# Universal_receiver.net
KiCad netlist of a schematic drawn in Altium Designer
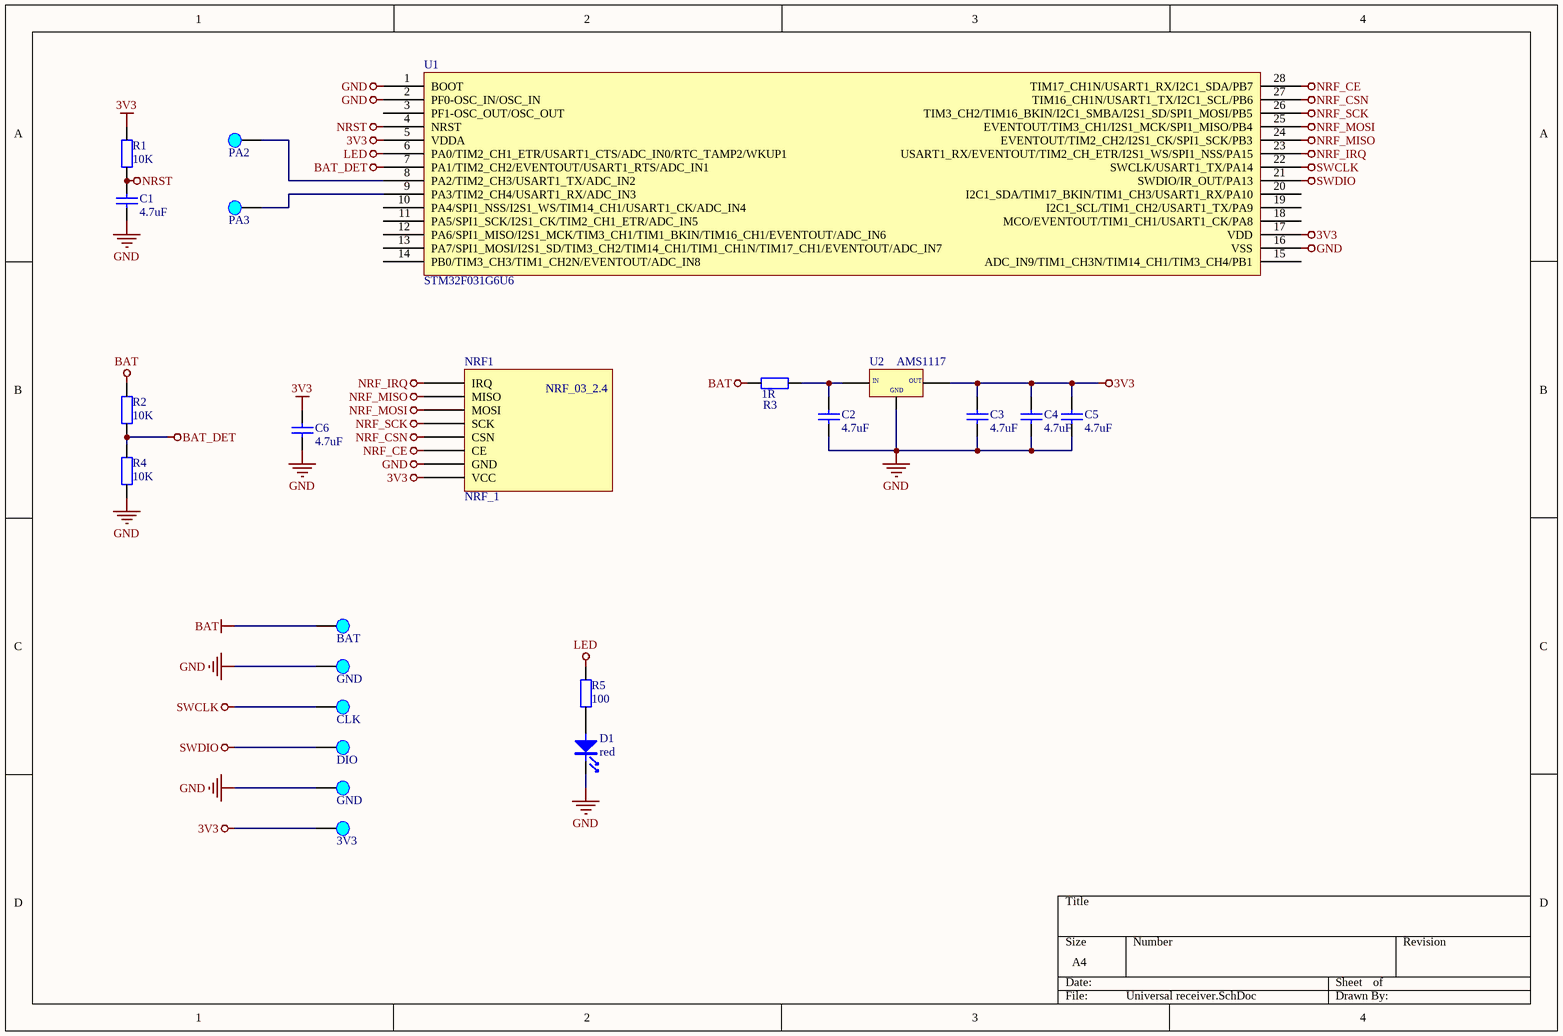
[diagram p0: Universal receiver.SchDoc]

(export (version "E")
  (design (tool "Eeschema 10.0.6"))
  (components
    (comp (ref "1")
      (value "3V3")
      (footprint "Pad_B")
      (fields (field (name "_REMARKS") "3V3"))
      (libsource (lib "元件库") (part "Pad"))
    )
    (comp (ref "BAT1")
      (value "BAT")
      (footprint "Pad_B")
      (fields (field (name "_REMARKS") "BAT"))
      (libsource (lib "元件库") (part "Pad"))
    )
    (comp (ref "C1")
      (value "4.7uF")
      (footprint "Watch Max:电容_C0603")
      (fields (field (name "C") "4.7uF"))
      (libsource (lib "WatchX") (part "cap"))
    )
    (comp (ref "C2")
      (value "4.7uF")
      (footprint "Watch Max:电容_C0603")
      (fields (field (name "C") "4.7uF"))
      (libsource (lib "WatchX") (part "cap"))
    )
    (comp (ref "C3")
      (value "4.7uF")
      (footprint "Watch Max:电容_C0603")
      (fields (field (name "C") "4.7uF"))
      (libsource (lib "WatchX") (part "cap"))
    )
    (comp (ref "C4")
      (value "4.7uF")
      (footprint "Watch Max:电容_C0603")
      (fields (field (name "C") "4.7uF"))
      (libsource (lib "WatchX") (part "cap"))
    )
    (comp (ref "C5")
      (value "4.7uF")
      (footprint "Watch Max:电容_C0603")
      (fields (field (name "C") "4.7uF"))
      (libsource (lib "WatchX") (part "cap"))
    )
    (comp (ref "C6")
      (value "4.7uF")
      (footprint "Watch Max:电容_C0603")
      (fields (field (name "C") "4.7uF"))
      (libsource (lib "WatchX") (part "cap"))
    )
    (comp (ref "CLK1")
      (value "CLK")
      (footprint "Pad_B")
      (fields (field (name "_REMARKS") "CLK"))
      (libsource (lib "元件库") (part "Pad"))
    )
    (comp (ref "D1")
      (value "red")
      (footprint "LED_0603")
      (libsource (lib "altium-import") (part "root_0_LED_"))
    )
    (comp (ref "DIO1")
      (value "DIO")
      (footprint "Pad_B")
      (fields (field (name "_REMARKS") "DIO"))
      (libsource (lib "元件库") (part "Pad"))
    )
    (comp (ref "GND1")
      (value "GND")
      (footprint "Pad_B")
      (fields (field (name "_REMARKS") "GND"))
      (libsource (lib "元件库") (part "Pad"))
    )
    (comp (ref "GND2")
      (value "GND")
      (footprint "Pad_B")
      (fields (field (name "_REMARKS") "GND"))
      (libsource (lib "元件库") (part "Pad"))
    )
    (comp (ref "NRF1") (value "NRF_1") (footprint "NRF-1") (libsource (lib "Schlib1") (part "NRF_1")))
    (comp (ref "PA1")
      (value "PA2")
      (footprint "Pad_B")
      (fields (field (name "_REMARKS") "PA2"))
      (libsource (lib "元件库") (part "Pad"))
    )
    (comp (ref "PA2")
      (value "PA3")
      (footprint "Pad_B")
      (fields (field (name "_REMARKS") "PA3"))
      (libsource (lib "元件库") (part "Pad"))
    )
    (comp (ref "R1")
      (value "10K")
      (footprint "电阻_R0603")
      (fields (field (name "R") "10K"))
      (libsource (lib "元件库") (part "Res"))
    )
    (comp (ref "R2")
      (value "10K")
      (footprint "电阻_R0603")
      (fields (field (name "R") "10K"))
      (libsource (lib "元件库") (part "Res"))
    )
    (comp (ref "R3")
      (value "1R")
      (footprint "电阻_R0603")
      (fields (field (name "R") "1R"))
      (libsource (lib "") (part "Res_2"))
    )
    (comp (ref "R4")
      (value "10K")
      (footprint "电阻_R0603")
      (fields (field (name "R") "10K"))
      (libsource (lib "元件库") (part "Res"))
    )
    (comp (ref "R5")
      (value "100")
      (footprint "电阻_R0603")
      (fields (field (name "R") "100"))
      (libsource (lib "") (part "Res_1"))
    )
    (comp (ref "U1")
      (value "STM32F031G6U6")
      (footprint "ST主控_UFQFPN28")
      (libsource (lib "Dj140") (part "STM32F031G6U6"))
    )
    (comp (ref "U2") (value "AMS1117") (footprint "稳压芯片_SOT-89") (libsource (lib "元件库") (part "AMS1117")))
  )
  (nets
    (net (code "1") (name "3V3") (class "Default")
      (node (ref "1") (pin "1") (pinfunction "*_1") (pintype "passive"))
      (node (ref "C3") (pin "2") (pinfunction "2_2") (pintype "passive"))
      (node (ref "C4") (pin "2") (pinfunction "2_2") (pintype "passive"))
      (node (ref "C5") (pin "2") (pinfunction "2_2") (pintype "passive"))
      (node (ref "C6") (pin "2") (pinfunction "2_2") (pintype "passive"))
      (node (ref "NRF1") (pin "1") (pinfunction "VCC_1") (pintype "passive"))
      (node (ref "R1") (pin "2") (pinfunction "2_2") (pintype "passive"))
      (node (ref "U1") (pin "17") (pinfunction "VDD_17") (pintype "passive"))
      (node (ref "U1") (pin "5") (pinfunction "VDDA_5") (pintype "passive"))
      (node (ref "U2") (pin "2") (pinfunction "OUT_2") (pintype "passive"))
    )
    (net (code "2") (name "BAT") (class "Default")
      (node (ref "BAT1") (pin "1") (pinfunction "*_1") (pintype "passive"))
      (node (ref "R2") (pin "2") (pinfunction "2_2") (pintype "passive"))
      (node (ref "R3") (pin "1") (pinfunction "1_1") (pintype "passive"))
    )
    (net (code "3") (name "BAT_DET") (class "Default")
      (node (ref "R2") (pin "1") (pinfunction "1_1") (pintype "passive"))
      (node (ref "R4") (pin "2") (pinfunction "2_2") (pintype "passive"))
      (node (ref "U1") (pin "7") (pinfunction "PA1/TIM2_CH2/EVENTOUT/USART1_RTS/ADC_IN1_7") (pintype "passive"))
    )
    (net (code "4") (name "GND") (class "Default")
      (node (ref "C1") (pin "1") (pinfunction "1_1") (pintype "passive"))
      (node (ref "C2") (pin "1") (pinfunction "1_1") (pintype "passive"))
      (node (ref "C3") (pin "1") (pinfunction "1_1") (pintype "passive"))
      (node (ref "C4") (pin "1") (pinfunction "1_1") (pintype "passive"))
      (node (ref "C5") (pin "1") (pinfunction "1_1") (pintype "passive"))
      (node (ref "C6") (pin "1") (pinfunction "1_1") (pintype "passive"))
      (node (ref "D1") (pin "K") (pinfunction "K_K") (pintype "passive"))
      (node (ref "GND1") (pin "1") (pinfunction "*_1") (pintype "passive"))
      (node (ref "GND2") (pin "1") (pinfunction "*_1") (pintype "passive"))
      (node (ref "NRF1") (pin "2") (pinfunction "GND_2") (pintype "passive"))
      (node (ref "R4") (pin "1") (pinfunction "1_1") (pintype "passive"))
      (node (ref "U1") (pin "1") (pinfunction "BOOT_1") (pintype "passive"))
      (node (ref "U1") (pin "16") (pinfunction "VSS_16") (pintype "passive"))
      (node (ref "U1") (pin "2") (pinfunction "PF0-OSC_IN/OSC_IN_2") (pintype "passive"))
      (node (ref "U2") (pin "1") (pinfunction "GND_1") (pintype "passive"))
    )
    (net (code "5") (name "LED") (class "Default")
      (node (ref "R5") (pin "1") (pinfunction "1_1") (pintype "passive"))
      (node (ref "U1") (pin "6") (pinfunction "PA0/TIM2_CH1_ETR/USART1_CTS/ADC_IN0/RTC_TAMP2/WKUP1_6") (pintype "passive"))
    )
    (net (code "6") (name "NRF_CE") (class "Default")
      (node (ref "NRF1") (pin "3") (pinfunction "CE_3") (pintype "passive"))
      (node (ref "U1") (pin "28") (pinfunction "TIM17_CH1N/USART1_RX/I2C1_SDA/PB7_28") (pintype "passive"))
    )
    (net (code "7") (name "NRF_CSN") (class "Default")
      (node (ref "NRF1") (pin "4") (pinfunction "CSN_4") (pintype "passive"))
      (node (ref "U1") (pin "27") (pinfunction "TIM16_CH1N/USART1_TX/I2C1_SCL/PB6_27") (pintype "passive"))
    )
    (net (code "8") (name "NRF_IRQ") (class "Default")
      (node (ref "NRF1") (pin "8") (pinfunction "IRQ_8") (pintype "passive"))
      (node (ref "U1") (pin "23") (pinfunction "USART1_RX/EVENTOUT/TIM2_CH_ETR/I2S1_WS/SPI1_NSS/PA15_23") (pintype "passive"))
    )
    (net (code "9") (name "NRF_MISO") (class "Default")
      (node (ref "NRF1") (pin "7") (pinfunction "MISO_7") (pintype "passive"))
      (node (ref "U1") (pin "24") (pinfunction "EVENTOUT/TIM2_CH2/I2S1_CK/SPI1_SCK/PB3_24") (pintype "passive"))
    )
    (net (code "10") (name "NRF_MOSI") (class "Default")
      (node (ref "NRF1") (pin "6") (pinfunction "MOSI_6") (pintype "passive"))
      (node (ref "U1") (pin "25") (pinfunction "EVENTOUT/TIM3_CH1/I2S1_MCK/SPI1_MISO/PB4_25") (pintype "passive"))
    )
    (net (code "11") (name "NRF_SCK") (class "Default")
      (node (ref "NRF1") (pin "5") (pinfunction "SCK_5") (pintype "passive"))
      (node (ref "U1") (pin "26") (pinfunction "TIM3_CH2/TIM16_BKIN/I2C1_SMBA/I2S1_SD/SPI1_MOSI/PB5_26") (pintype "passive"))
    )
    (net (code "12") (name "NRST") (class "Default")
      (node (ref "C1") (pin "2") (pinfunction "2_2") (pintype "passive"))
      (node (ref "R1") (pin "1") (pinfunction "1_1") (pintype "passive"))
      (node (ref "U1") (pin "4") (pinfunction "NRST_4") (pintype "passive"))
    )
    (net (code "13") (name "Net-(D1-PadA)") (class "Default")
      (node (ref "D1") (pin "A") (pinfunction "A_A") (pintype "passive"))
      (node (ref "R5") (pin "2") (pinfunction "2_2") (pintype "passive"))
    )
    (net (code "14") (name "Net-(PA1-*)") (class "Default")
      (node (ref "PA1") (pin "1") (pinfunction "*_1") (pintype "passive"))
      (node (ref "U1") (pin "8") (pinfunction "PA2/TIM2_CH3/USART1_TX/ADC_IN2_8") (pintype "passive"))
    )
    (net (code "15") (name "Net-(PA2-*)") (class "Default")
      (node (ref "PA2") (pin "1") (pinfunction "*_1") (pintype "passive"))
      (node (ref "U1") (pin "9") (pinfunction "PA3/TIM2_CH4/USART1_RX/ADC_IN3_9") (pintype "passive"))
    )
    (net (code "16") (name "Net-(U2-VIN)") (class "Default")
      (node (ref "C2") (pin "2") (pinfunction "2_2") (pintype "passive"))
      (node (ref "R3") (pin "2") (pinfunction "2_2") (pintype "passive"))
      (node (ref "U2") (pin "3") (pinfunction "VIN_3") (pintype "passive"))
    )
    (net (code "17") (name "SWCLK") (class "Default")
      (node (ref "CLK1") (pin "1") (pinfunction "*_1") (pintype "passive"))
      (node (ref "U1") (pin "22") (pinfunction "SWCLK/USART1_TX/PA14_22") (pintype "passive"))
    )
    (net (code "18") (name "SWDIO") (class "Default")
      (node (ref "DIO1") (pin "1") (pinfunction "*_1") (pintype "passive"))
      (node (ref "U1") (pin "21") (pinfunction "SWDIO/IR_OUT/PA13_21") (pintype "passive"))
    )
    (net (code "19") (name "unconnected-(U1-ADC_IN9{slash}TIM1_CH3N{slash}TIM14_CH1{slash}TIM3_CH4{slash}PB1-Pad15)") (class "Default")
      (node (ref "U1") (pin "15") (pinfunction "ADC_IN9/TIM1_CH3N/TIM14_CH1/TIM3_CH4/PB1_15") (pintype "passive"))
    )
    (net (code "20") (name "unconnected-(U1-I2C1_SCL{slash}TIM1_CH2{slash}USART1_TX{slash}PA9-Pad19)") (class "Default")
      (node (ref "U1") (pin "19") (pinfunction "I2C1_SCL/TIM1_CH2/USART1_TX/PA9_19") (pintype "passive"))
    )
    (net (code "21") (name "unconnected-(U1-I2C1_SDA{slash}TIM17_BKIN{slash}TIM1_CH3{slash}USART1_RX{slash}PA10-Pad20)") (class "Default")
      (node (ref "U1") (pin "20") (pinfunction "I2C1_SDA/TIM17_BKIN/TIM1_CH3/USART1_RX/PA10_20") (pintype "passive"))
    )
    (net (code "22") (name "unconnected-(U1-MCO{slash}EVENTOUT{slash}TIM1_CH1{slash}USART1_CK{slash}PA8-Pad18)") (class "Default")
      (node (ref "U1") (pin "18") (pinfunction "MCO/EVENTOUT/TIM1_CH1/USART1_CK/PA8_18") (pintype "passive"))
    )
    (net (code "23") (name "unconnected-(U1-PA4{slash}SPI1_NSS{slash}I2S1_WS{slash}TIM14_CH1{slash}USART1_CK{slash}ADC_IN4-Pad10)") (class "Default")
      (node (ref "U1") (pin "10") (pinfunction "PA4/SPI1_NSS/I2S1_WS/TIM14_CH1/USART1_CK/ADC_IN4_10") (pintype "passive"))
    )
    (net (code "24") (name "unconnected-(U1-PA5{slash}SPI1_SCK{slash}I2S1_CK{slash}TIM2_CH1_ETR{slash}ADC_IN5-Pad11)") (class "Default")
      (node (ref "U1") (pin "11") (pinfunction "PA5/SPI1_SCK/I2S1_CK/TIM2_CH1_ETR/ADC_IN5_11") (pintype "passive"))
    )
    (net (code "25") (name "unconnected-(U1-PA6{slash}SPI1_MISO{slash}I2S1_MCK{slash}TIM3_CH1{slash}TIM1_BKIN{slash}TIM16_CH1{slash}EVENTOUT{slash}ADC_IN6-Pad12)") (class "Default")
      (node (ref "U1") (pin "12") (pinfunction "PA6/SPI1_MISO/I2S1_MCK/TIM3_CH1/TIM1_BKIN/TIM16_CH1/EVENTOUT/ADC_IN6_12") (pintype "passive"))
    )
    (net (code "26") (name "unconnected-(U1-PA7{slash}SPI1_MOSI{slash}I2S1_SD{slash}TIM3_CH2{slash}TIM14_CH1{slash}TIM1_CH1N{slash}TIM17_CH1{slash}EVENTOUT{slash}ADC_IN7-Pad13)") (class "Default")
      (node (ref "U1") (pin "13") (pinfunction "PA7/SPI1_MOSI/I2S1_SD/TIM3_CH2/TIM14_CH1/TIM1_CH1N/TIM17_CH1/EVENTOUT/ADC_IN7_13") (pintype "passive"))
    )
    (net (code "27") (name "unconnected-(U1-PB0{slash}TIM3_CH3{slash}TIM1_CH2N{slash}EVENTOUT{slash}ADC_IN8-Pad14)") (class "Default")
      (node (ref "U1") (pin "14") (pinfunction "PB0/TIM3_CH3/TIM1_CH2N/EVENTOUT/ADC_IN8_14") (pintype "passive"))
    )
    (net (code "28") (name "unconnected-(U1-PF1-OSC_OUT{slash}OSC_OUT-Pad3)") (class "Default")
      (node (ref "U1") (pin "3") (pinfunction "PF1-OSC_OUT/OSC_OUT_3") (pintype "passive"))
    )
  )
)
